# MINI54_breakout.net
KiCad netlist of a schematic drawn in EAGLE
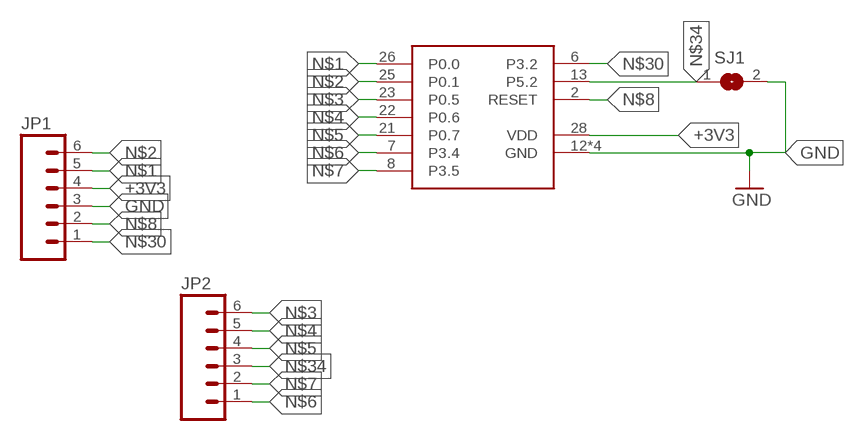
[diagram p0: schematic, sheet 1]

(export (version "E")
  (design (tool "Eeschema 10.0.6"))
  (components
    (comp (ref "JP1")
      (value "M06LONGPADS")
      (footprint "eagle-import:1X06_LONGPADS")
      (libsource (lib "eagle-import") (part "M06LONGPADS"))
    )
    (comp (ref "JP2")
      (value "M06LONGPADS")
      (footprint "eagle-import:1X06_LONGPADS")
      (libsource (lib "eagle-import") (part "M06LONGPADS"))
    )
    (comp (ref "SJ1") (value "SJ") (footprint "eagle-import:SJ") (libsource (lib "eagle-import") (part "SJ")))
    (comp (ref "U$9")
      (value "MINITAN54-QFN")
      (footprint "eagle-import:QFN50P500X500X100-33N")
      (libsource (lib "eagle-import") (part "MINITAN54-QFN"))
    )
  )
  (nets
    (net (code "1") (name "+3V3") (class "Default")
      (node (ref "JP1") (pin "4") (pinfunction "4_4") (pintype "passive"))
      (node (ref "U$9") (pin "28") (pinfunction "VDD_28") (pintype "bidirectional"))
    )
    (net (code "2") (name "GND") (class "Default")
      (node (ref "JP1") (pin "3") (pinfunction "3_3") (pintype "passive"))
      (node (ref "SJ1") (pin "2") (pinfunction "2_2") (pintype "passive"))
      (node (ref "U$9") (pin "12") (pinfunction "GND_12") (pintype "bidirectional"))
      (node (ref "U$9") (pin "17") (pinfunction "GND_17") (pintype "bidirectional"))
      (node (ref "U$9") (pin "32") (pinfunction "GND_32") (pintype "bidirectional"))
      (node (ref "U$9") (pin "33") (pinfunction "GND_33") (pintype "bidirectional"))
    )
    (net (code "3") (name "N$1") (class "Default")
      (node (ref "JP1") (pin "5") (pinfunction "5_5") (pintype "passive"))
      (node (ref "U$9") (pin "26") (pinfunction "P0.0_26") (pintype "bidirectional"))
    )
    (net (code "4") (name "N$2") (class "Default")
      (node (ref "JP1") (pin "6") (pinfunction "6_6") (pintype "passive"))
      (node (ref "U$9") (pin "25") (pinfunction "P0.1_25") (pintype "bidirectional"))
    )
    (net (code "5") (name "N$3") (class "Default")
      (node (ref "JP2") (pin "6") (pinfunction "6_6") (pintype "passive"))
      (node (ref "U$9") (pin "23") (pinfunction "P0.5_23") (pintype "bidirectional"))
    )
    (net (code "6") (name "N$4") (class "Default")
      (node (ref "JP2") (pin "5") (pinfunction "5_5") (pintype "passive"))
      (node (ref "U$9") (pin "22") (pinfunction "P0.6_22") (pintype "bidirectional"))
    )
    (net (code "7") (name "N$5") (class "Default")
      (node (ref "JP2") (pin "4") (pinfunction "4_4") (pintype "passive"))
      (node (ref "U$9") (pin "21") (pinfunction "P0.7_21") (pintype "bidirectional"))
    )
    (net (code "8") (name "N$6") (class "Default")
      (node (ref "JP2") (pin "1") (pinfunction "1_1") (pintype "passive"))
      (node (ref "U$9") (pin "7") (pinfunction "P3.4_7") (pintype "bidirectional"))
    )
    (net (code "9") (name "N$7") (class "Default")
      (node (ref "JP2") (pin "2") (pinfunction "2_2") (pintype "passive"))
      (node (ref "U$9") (pin "8") (pinfunction "P3.5_8") (pintype "bidirectional"))
    )
    (net (code "10") (name "N$8") (class "Default")
      (node (ref "JP1") (pin "2") (pinfunction "2_2") (pintype "passive"))
      (node (ref "U$9") (pin "2") (pinfunction "RESET_2") (pintype "bidirectional"))
    )
    (net (code "11") (name "N$30") (class "Default")
      (node (ref "JP1") (pin "1") (pinfunction "1_1") (pintype "passive"))
      (node (ref "U$9") (pin "6") (pinfunction "P3.2_6") (pintype "bidirectional"))
    )
    (net (code "12") (name "N$34") (class "Default")
      (node (ref "JP2") (pin "3") (pinfunction "3_3") (pintype "passive"))
      (node (ref "SJ1") (pin "1") (pinfunction "1_1") (pintype "passive"))
      (node (ref "U$9") (pin "13") (pinfunction "P5.2_13") (pintype "bidirectional"))
    )
  )
)
